# RFUSBtoDB15Adapter.net
KiCad netlist of a schematic drawn in EAGLE
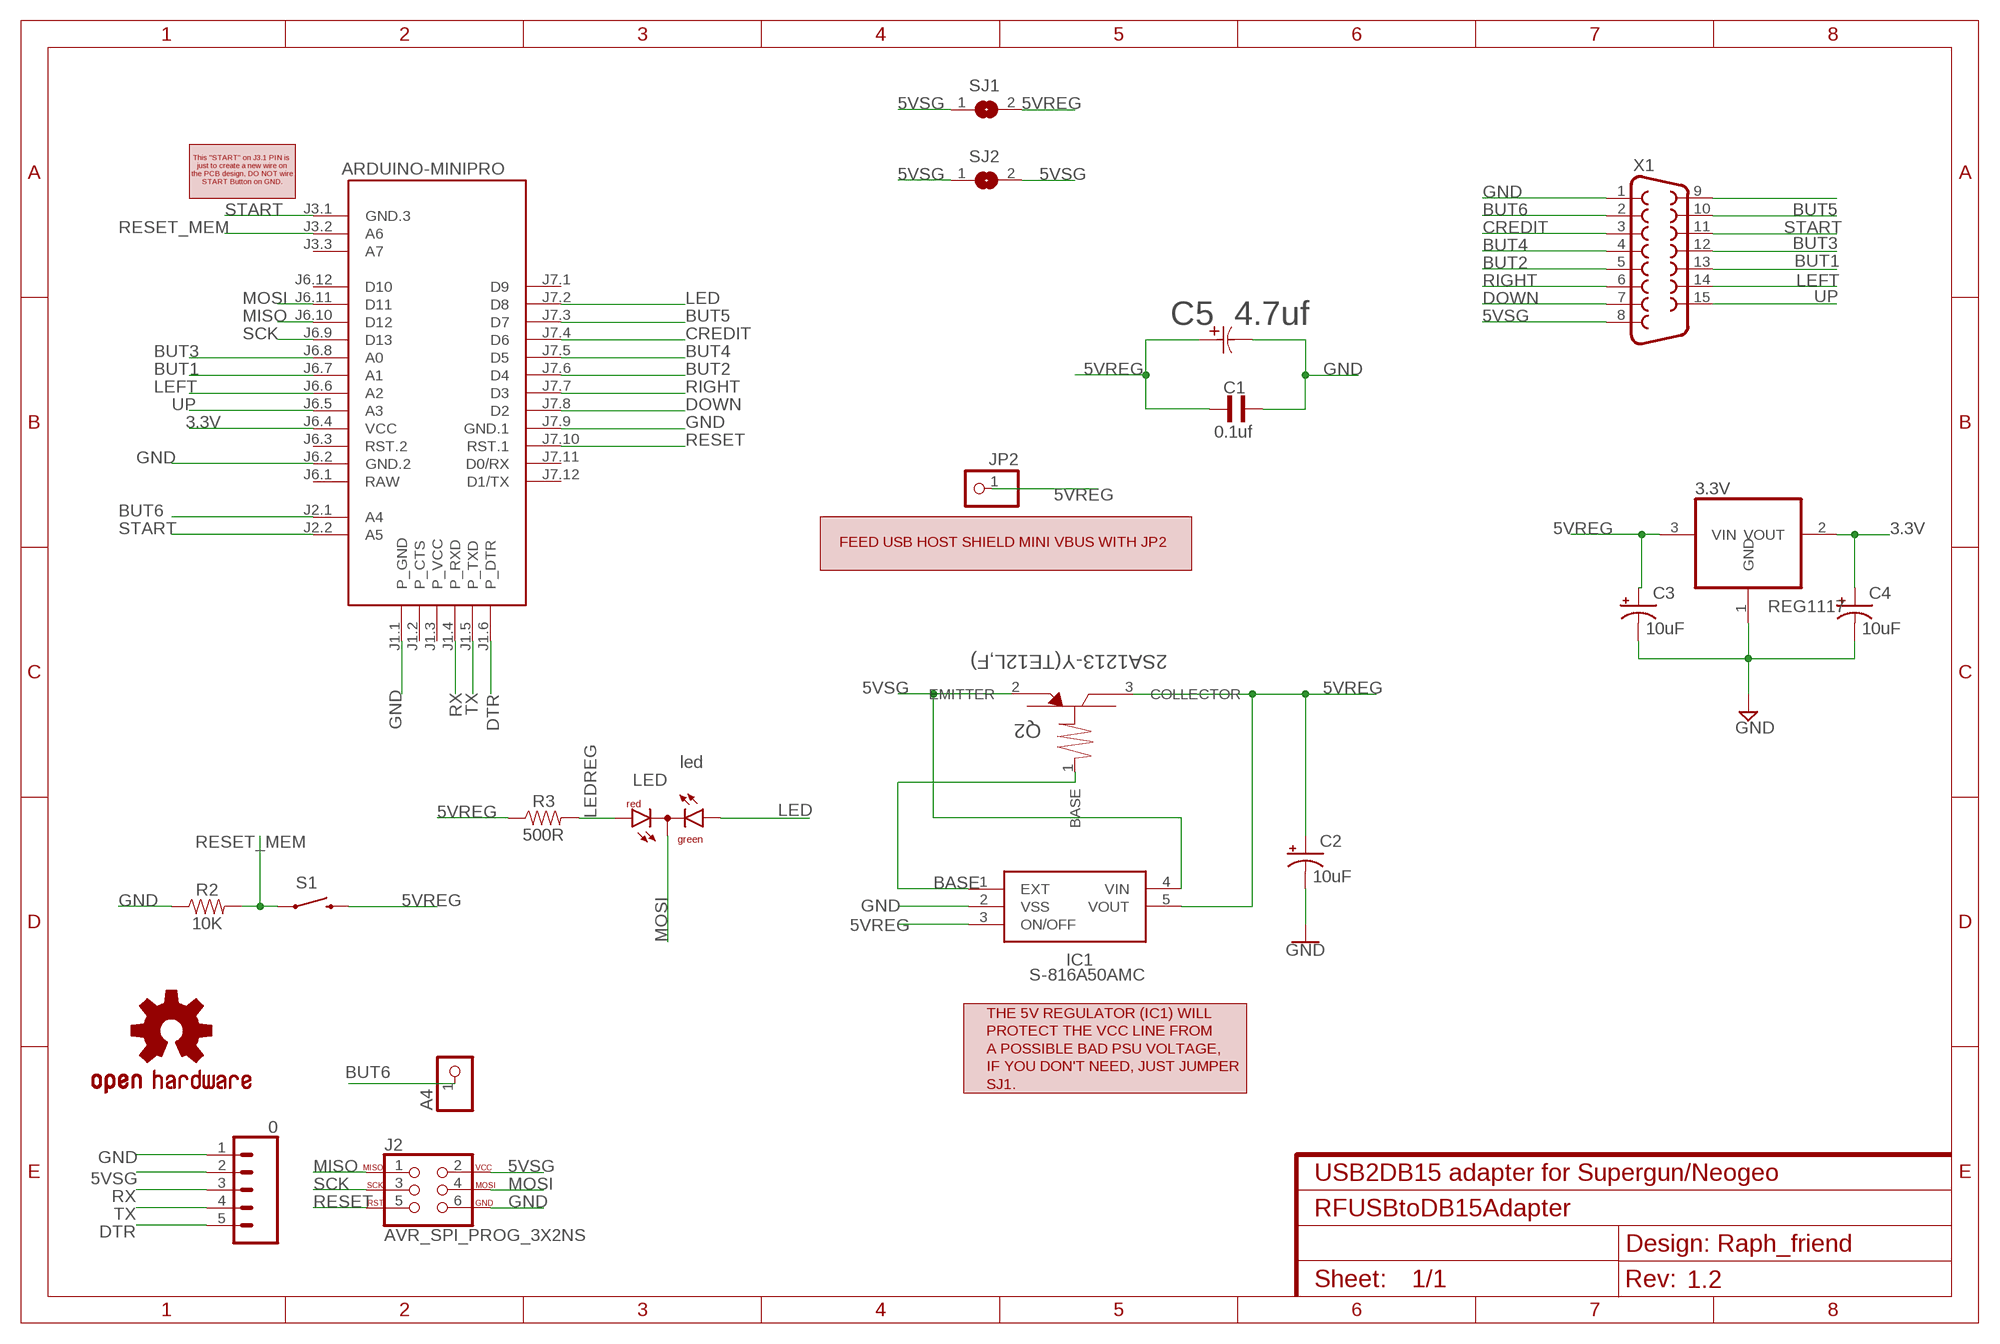
[diagram p0: schematic, sheet 1]

(export (version "E")
  (design (tool "Eeschema 10.0.6"))
  (components
    (comp (ref "3.3V")
      (value "REG1117")
      (footprint "eagle-import:SOT223")
      (libsource (lib "eagle-import") (part "REG1117"))
    )
    (comp (ref "A4")
      (value "0")
      (footprint "eagle-import:1X01")
      (libsource (lib "eagle-import") (part "PINHD-1X1"))
    )
    (comp (ref "ARDUINO-MINIPRO")
      (value "ARDUINO-PRO-MINI-5.0V")
      (footprint "eagle-import:ARDUINO-PRO-MINI")
      (libsource (lib "eagle-import") (part "ARDUINO-PRO-MINI-5.0V"))
    )
    (comp (ref "C1")
      (value "0.1uf")
      (footprint "eagle-import:WCAP-CSGP_0805_REFLOW")
      (libsource (lib "eagle-import") (part "WCAP-CSGP_0805_REFLOW_885012006082"))
    )
    (comp (ref "C2")
      (value "10uF")
      (footprint "eagle-import:EIA3216")
      (libsource (lib "eagle-import") (part "10UF-POLAR-EIA3216-16V-10%(TANT)"))
    )
    (comp (ref "C3")
      (value "10uF")
      (footprint "eagle-import:EIA3216")
      (libsource (lib "eagle-import") (part "10UF-POLAR-EIA3216-16V-10%(TANT)"))
    )
    (comp (ref "C4")
      (value "10uF")
      (footprint "eagle-import:EIA3216")
      (libsource (lib "eagle-import") (part "10UF-POLAR-EIA3216-16V-10%(TANT)"))
    )
    (comp (ref "C5")
      (value "4.7uf")
      (footprint "eagle-import:CAPMP3.4X1.6_1.8N_KEM")
      (fields (field (name "MANUFACTURER_PART_NUMBER") "T491A475K010AT"))
      (libsource (lib "eagle-import") (part "T491A475K010AT"))
    )
    (comp (ref "IC1")
      (value "S-816A40AMC-BAPT2U")
      (footprint "eagle-import:SOT95P275X130-5N")
      (fields
        (field (name "MANUFACTURER_PART_NUMBER") "S-816A40AMC-BAPT2U")
        (field (name "MOUSER_PART_NUMBER") "628-816A40AMC-G")
        (field (name "MANUFACTURER_PART_NUMBER_1") "S-816A50AMC")
      )
      (libsource (lib "eagle-import") (part "S-816A40AMC-BAPT2U"))
    )
    (comp (ref "J1")
      (value "0")
      (footprint "eagle-import:1X05")
      (libsource (lib "eagle-import") (part "CONN_05"))
    )
    (comp (ref "J2")
      (value "AVR_SPI_PROG_3X2NS")
      (footprint "eagle-import:2X3-NS")
      (libsource (lib "eagle-import") (part "AVR_SPI_PROG_3X2NS"))
    )
    (comp (ref "JP2")
      (value "JP2")
      (footprint "eagle-import:1X01")
      (libsource (lib "eagle-import") (part "PINHD-1X1"))
    )
    (comp (ref "LED")
      (value "led")
      (footprint "eagle-import:DUOLED-C-5MM")
      (libsource (lib "eagle-import") (part "DUOLED-RG-C"))
    )
    (comp (ref "LOGO1")
      (value "OSHW-LOGOS")
      (footprint "eagle-import:OSHW-LOGO-S")
      (libsource (lib "eagle-import") (part "OSHW-LOGOS"))
    )
    (comp (ref "Q2")
      (value "2SA1213-Y(TE12L,F)")
      (footprint "eagle-import:PW-MINI_TOS")
      (fields
        (field (name "MANUFACTURER_PART_NUMBER") "2SA1213-Y")
        (field (name "COPYRIGHT") "Copyright (C) 2018 Accelerated Designs. All rights reserved")
      )
      (libsource (lib "eagle-import") (part "2SA1213-Y(TE12L,F)"))
    )
    (comp (ref "R2")
      (value "10K")
      (footprint "eagle-import:0805")
      (libsource (lib "eagle-import") (part "0.3OHM-0805-1/8W-1%"))
    )
    (comp (ref "R3")
      (value "500R")
      (footprint "eagle-import:0805")
      (libsource (lib "eagle-import") (part "0.3OHM-0805-1/8W-1%"))
    )
    (comp (ref "S1")
      (value "RS032G05A3SM-SPST-MOMENTARY-SWSMD-1101NE")
      (footprint "eagle-import:TACTILE-SWITCH-1101NE")
      (libsource (lib "eagle-import") (part "RS032G05A3SM-SPST-MOMENTARY-SWSMD-1101NE"))
    )
    (comp (ref "SJ1") (value "SJ") (footprint "eagle-import:SJ") (libsource (lib "eagle-import") (part "SJ")))
    (comp (ref "SJ2") (value "SJ") (footprint "eagle-import:SJ") (libsource (lib "eagle-import") (part "SJ")))
    (comp (ref "X1")
      (value "F15HP")
      (footprint "eagle-import:F15HP")
      (libsource (lib "eagle-import") (part "F15HP"))
    )
  )
  (nets
    (net (code "1") (name "/3.3V") (class "Default")
      (node (ref "3.3V") (pin "2") (pinfunction "VOUT_2") (pintype "output"))
      (node (ref "ARDUINO-MINIPRO") (pin "J6.4") (pinfunction "VCC_J6.4") (pintype "power_in"))
      (node (ref "C4") (pin "+") (pinfunction "+_+") (pintype "passive"))
    )
    (net (code "2") (name "/5VREG") (class "Default")
      (node (ref "3.3V") (pin "3") (pinfunction "VIN_3") (pintype "input"))
      (node (ref "C1") (pin "2") (pinfunction "2_2") (pintype "passive"))
      (node (ref "C2") (pin "+") (pinfunction "+_+") (pintype "passive"))
      (node (ref "C3") (pin "+") (pinfunction "+_+") (pintype "passive"))
      (node (ref "C5") (pin "1") (pinfunction "1_1") (pintype "passive"))
      (node (ref "IC1") (pin "3") (pinfunction "ON/OFF_3") (pintype "bidirectional"))
      (node (ref "IC1") (pin "5") (pinfunction "VOUT_5") (pintype "bidirectional"))
      (node (ref "JP2") (pin "1") (pinfunction "1_1") (pintype "passive"))
      (node (ref "Q2") (pin "3") (pinfunction "COLLECTOR_3") (pintype "passive"))
      (node (ref "R3") (pin "1") (pinfunction "1_1") (pintype "passive"))
      (node (ref "S1") (pin "2") (pinfunction "2_2") (pintype "passive"))
      (node (ref "SJ1") (pin "2") (pinfunction "2_2") (pintype "passive"))
    )
    (net (code "3") (name "/5VSG") (class "Default")
      (node (ref "IC1") (pin "4") (pinfunction "VIN_4") (pintype "bidirectional"))
      (node (ref "J1") (pin "2") (pinfunction "2_2") (pintype "passive"))
      (node (ref "J2") (pin "2") (pinfunction "2_2") (pintype "passive"))
      (node (ref "Q2") (pin "2") (pinfunction "EMITTER_2") (pintype "passive"))
      (node (ref "SJ1") (pin "1") (pinfunction "1_1") (pintype "passive"))
      (node (ref "SJ2") (pin "1") (pinfunction "1_1") (pintype "passive"))
      (node (ref "SJ2") (pin "2") (pinfunction "2_2") (pintype "passive"))
      (node (ref "X1") (pin "8") (pinfunction "8_8") (pintype "passive"))
    )
    (net (code "4") (name "/BASE") (class "Default")
      (node (ref "IC1") (pin "1") (pinfunction "EXT_1") (pintype "bidirectional"))
      (node (ref "Q2") (pin "1") (pinfunction "BASE_1") (pintype "passive"))
    )
    (net (code "5") (name "/BUT1") (class "Default")
      (node (ref "ARDUINO-MINIPRO") (pin "J6.7") (pinfunction "A1_J6.7") (pintype "bidirectional"))
      (node (ref "X1") (pin "13") (pinfunction "13_13") (pintype "passive"))
    )
    (net (code "6") (name "/BUT2") (class "Default")
      (node (ref "ARDUINO-MINIPRO") (pin "J7.6") (pinfunction "D4_J7.6") (pintype "bidirectional"))
      (node (ref "X1") (pin "5") (pinfunction "5_5") (pintype "passive"))
    )
    (net (code "7") (name "/BUT3") (class "Default")
      (node (ref "ARDUINO-MINIPRO") (pin "J6.8") (pinfunction "A0_J6.8") (pintype "bidirectional"))
      (node (ref "X1") (pin "12") (pinfunction "12_12") (pintype "passive"))
    )
    (net (code "8") (name "/BUT4") (class "Default")
      (node (ref "ARDUINO-MINIPRO") (pin "J7.5") (pinfunction "D5_J7.5") (pintype "bidirectional"))
      (node (ref "X1") (pin "4") (pinfunction "4_4") (pintype "passive"))
    )
    (net (code "9") (name "/BUT5") (class "Default")
      (node (ref "ARDUINO-MINIPRO") (pin "J7.3") (pinfunction "D7_J7.3") (pintype "bidirectional"))
      (node (ref "X1") (pin "10") (pinfunction "10_10") (pintype "passive"))
    )
    (net (code "10") (name "/BUT6") (class "Default")
      (node (ref "A4") (pin "1") (pinfunction "1_1") (pintype "passive"))
      (node (ref "ARDUINO-MINIPRO") (pin "J2.1") (pinfunction "A4_J2.1") (pintype "bidirectional"))
      (node (ref "X1") (pin "2") (pinfunction "2_2") (pintype "passive"))
    )
    (net (code "11") (name "/CREDIT") (class "Default")
      (node (ref "ARDUINO-MINIPRO") (pin "J7.4") (pinfunction "D6_J7.4") (pintype "bidirectional"))
      (node (ref "X1") (pin "3") (pinfunction "3_3") (pintype "passive"))
    )
    (net (code "12") (name "/DOWN") (class "Default")
      (node (ref "ARDUINO-MINIPRO") (pin "J7.8") (pinfunction "D2_J7.8") (pintype "bidirectional"))
      (node (ref "X1") (pin "7") (pinfunction "7_7") (pintype "passive"))
    )
    (net (code "13") (name "/DTR") (class "Default")
      (node (ref "ARDUINO-MINIPRO") (pin "J1.6") (pinfunction "P_DTR_J1.6") (pintype "bidirectional"))
      (node (ref "J1") (pin "5") (pinfunction "5_5") (pintype "passive"))
    )
    (net (code "14") (name "/LED") (class "Default")
      (node (ref "ARDUINO-MINIPRO") (pin "J7.2") (pinfunction "D8_J7.2") (pintype "bidirectional"))
      (node (ref "LED") (pin "AX") (pinfunction "AG_AX") (pintype "passive"))
    )
    (net (code "15") (name "/LEDREG") (class "Default")
      (node (ref "LED") (pin "AR") (pinfunction "AR_AR") (pintype "passive"))
      (node (ref "R3") (pin "2") (pinfunction "2_2") (pintype "passive"))
    )
    (net (code "16") (name "/LEFT") (class "Default")
      (node (ref "ARDUINO-MINIPRO") (pin "J6.6") (pinfunction "A2_J6.6") (pintype "bidirectional"))
      (node (ref "X1") (pin "14") (pinfunction "14_14") (pintype "passive"))
    )
    (net (code "17") (name "/MISO") (class "Default")
      (node (ref "ARDUINO-MINIPRO") (pin "J6.10") (pinfunction "D12_J6.10") (pintype "bidirectional"))
      (node (ref "J2") (pin "1") (pinfunction "1_1") (pintype "passive"))
    )
    (net (code "18") (name "/MOSI") (class "Default")
      (node (ref "ARDUINO-MINIPRO") (pin "J6.11") (pinfunction "D11_J6.11") (pintype "bidirectional"))
      (node (ref "J2") (pin "4") (pinfunction "4_4") (pintype "passive"))
      (node (ref "LED") (pin "C") (pinfunction "C_C") (pintype "passive"))
    )
    (net (code "19") (name "/RAW") (class "Default")
      (node (ref "ARDUINO-MINIPRO") (pin "J6.1") (pinfunction "RAW_J6.1") (pintype "power_in"))
    )
    (net (code "20") (name "/RESET") (class "Default")
      (node (ref "ARDUINO-MINIPRO") (pin "J7.10") (pinfunction "RST.1_J7.10") (pintype "bidirectional"))
      (node (ref "J2") (pin "5") (pinfunction "5_5") (pintype "passive"))
    )
    (net (code "21") (name "/RESET_MEM") (class "Default")
      (node (ref "ARDUINO-MINIPRO") (pin "J3.2") (pinfunction "A6_J3.2") (pintype "bidirectional"))
      (node (ref "R2") (pin "2") (pinfunction "2_2") (pintype "passive"))
      (node (ref "S1") (pin "1") (pinfunction "1_1") (pintype "passive"))
    )
    (net (code "22") (name "/RIGHT") (class "Default")
      (node (ref "ARDUINO-MINIPRO") (pin "J7.7") (pinfunction "D3_J7.7") (pintype "bidirectional"))
      (node (ref "X1") (pin "6") (pinfunction "6_6") (pintype "passive"))
    )
    (net (code "23") (name "/RX") (class "Default")
      (node (ref "ARDUINO-MINIPRO") (pin "J1.4") (pinfunction "P_RXD_J1.4") (pintype "bidirectional"))
      (node (ref "J1") (pin "3") (pinfunction "3_3") (pintype "passive"))
    )
    (net (code "24") (name "/SCK") (class "Default")
      (node (ref "ARDUINO-MINIPRO") (pin "J6.9") (pinfunction "D13_J6.9") (pintype "bidirectional"))
      (node (ref "J2") (pin "3") (pinfunction "3_3") (pintype "passive"))
    )
    (net (code "25") (name "/START") (class "Default")
      (node (ref "ARDUINO-MINIPRO") (pin "J2.2") (pinfunction "A5_J2.2") (pintype "bidirectional"))
      (node (ref "ARDUINO-MINIPRO") (pin "J3.1") (pinfunction "GND.3_J3.1") (pintype "bidirectional"))
      (node (ref "X1") (pin "11") (pinfunction "11_11") (pintype "passive"))
    )
    (net (code "26") (name "/TX") (class "Default")
      (node (ref "ARDUINO-MINIPRO") (pin "J1.5") (pinfunction "P_TXD_J1.5") (pintype "bidirectional"))
      (node (ref "J1") (pin "4") (pinfunction "4_4") (pintype "passive"))
    )
    (net (code "27") (name "/UP") (class "Default")
      (node (ref "ARDUINO-MINIPRO") (pin "J6.5") (pinfunction "A3_J6.5") (pintype "bidirectional"))
      (node (ref "X1") (pin "15") (pinfunction "15_15") (pintype "passive"))
    )
    (net (code "28") (name "GND") (class "Default")
      (node (ref "3.3V") (pin "1") (pinfunction "GND_1") (pintype "power_in"))
      (node (ref "ARDUINO-MINIPRO") (pin "J1.1") (pinfunction "P_GND_J1.1") (pintype "bidirectional"))
      (node (ref "ARDUINO-MINIPRO") (pin "J6.2") (pinfunction "GND.2_J6.2") (pintype "power_in"))
      (node (ref "ARDUINO-MINIPRO") (pin "J7.9") (pinfunction "GND.1_J7.9") (pintype "power_in"))
      (node (ref "C1") (pin "1") (pinfunction "1_1") (pintype "passive"))
      (node (ref "C2") (pin "-") (pinfunction "-_-") (pintype "passive"))
      (node (ref "C3") (pin "-") (pinfunction "-_-") (pintype "passive"))
      (node (ref "C4") (pin "-") (pinfunction "-_-") (pintype "passive"))
      (node (ref "C5") (pin "2") (pinfunction "2_2") (pintype "passive"))
      (node (ref "IC1") (pin "2") (pinfunction "VSS_2") (pintype "bidirectional"))
      (node (ref "J1") (pin "1") (pinfunction "1_1") (pintype "passive"))
      (node (ref "J2") (pin "6") (pinfunction "6_6") (pintype "passive"))
      (node (ref "R2") (pin "1") (pinfunction "1_1") (pintype "passive"))
      (node (ref "X1") (pin "1") (pinfunction "1_1") (pintype "passive"))
    )
    (net (code "29") (name "unconnected-(ARDUINO-MINIPRO-A7-PadJ3.3)") (class "Default")
      (node (ref "ARDUINO-MINIPRO") (pin "J3.3") (pinfunction "A7_J3.3") (pintype "bidirectional"))
    )
    (net (code "30") (name "unconnected-(ARDUINO-MINIPRO-D0{slash}RX-PadJ7.11)") (class "Default")
      (node (ref "ARDUINO-MINIPRO") (pin "J7.11") (pinfunction "D0/RX_J7.11") (pintype "bidirectional"))
    )
    (net (code "31") (name "unconnected-(ARDUINO-MINIPRO-D1{slash}TX-PadJ7.12)") (class "Default")
      (node (ref "ARDUINO-MINIPRO") (pin "J7.12") (pinfunction "D1/TX_J7.12") (pintype "bidirectional"))
    )
    (net (code "32") (name "unconnected-(ARDUINO-MINIPRO-D9-PadJ7.1)") (class "Default")
      (node (ref "ARDUINO-MINIPRO") (pin "J7.1") (pinfunction "D9_J7.1") (pintype "bidirectional"))
    )
    (net (code "33") (name "unconnected-(ARDUINO-MINIPRO-D10-PadJ6.12)") (class "Default")
      (node (ref "ARDUINO-MINIPRO") (pin "J6.12") (pinfunction "D10_J6.12") (pintype "bidirectional"))
    )
    (net (code "34") (name "unconnected-(ARDUINO-MINIPRO-P_CTS-PadJ1.2)") (class "Default")
      (node (ref "ARDUINO-MINIPRO") (pin "J1.2") (pinfunction "P_CTS_J1.2") (pintype "bidirectional"))
    )
    (net (code "35") (name "unconnected-(ARDUINO-MINIPRO-P_VCC-PadJ1.3)") (class "Default")
      (node (ref "ARDUINO-MINIPRO") (pin "J1.3") (pinfunction "P_VCC_J1.3") (pintype "bidirectional"))
    )
    (net (code "36") (name "unconnected-(ARDUINO-MINIPRO-RST.2-PadJ6.3)") (class "Default")
      (node (ref "ARDUINO-MINIPRO") (pin "J6.3") (pinfunction "RST.2_J6.3") (pintype "bidirectional"))
    )
    (net (code "37") (name "unconnected-(X1-Pad9)") (class "Default")
      (node (ref "X1") (pin "9") (pinfunction "9_9") (pintype "passive"))
    )
  )
)
